# OpenLog.net
KiCad netlist of a schematic drawn in EAGLE
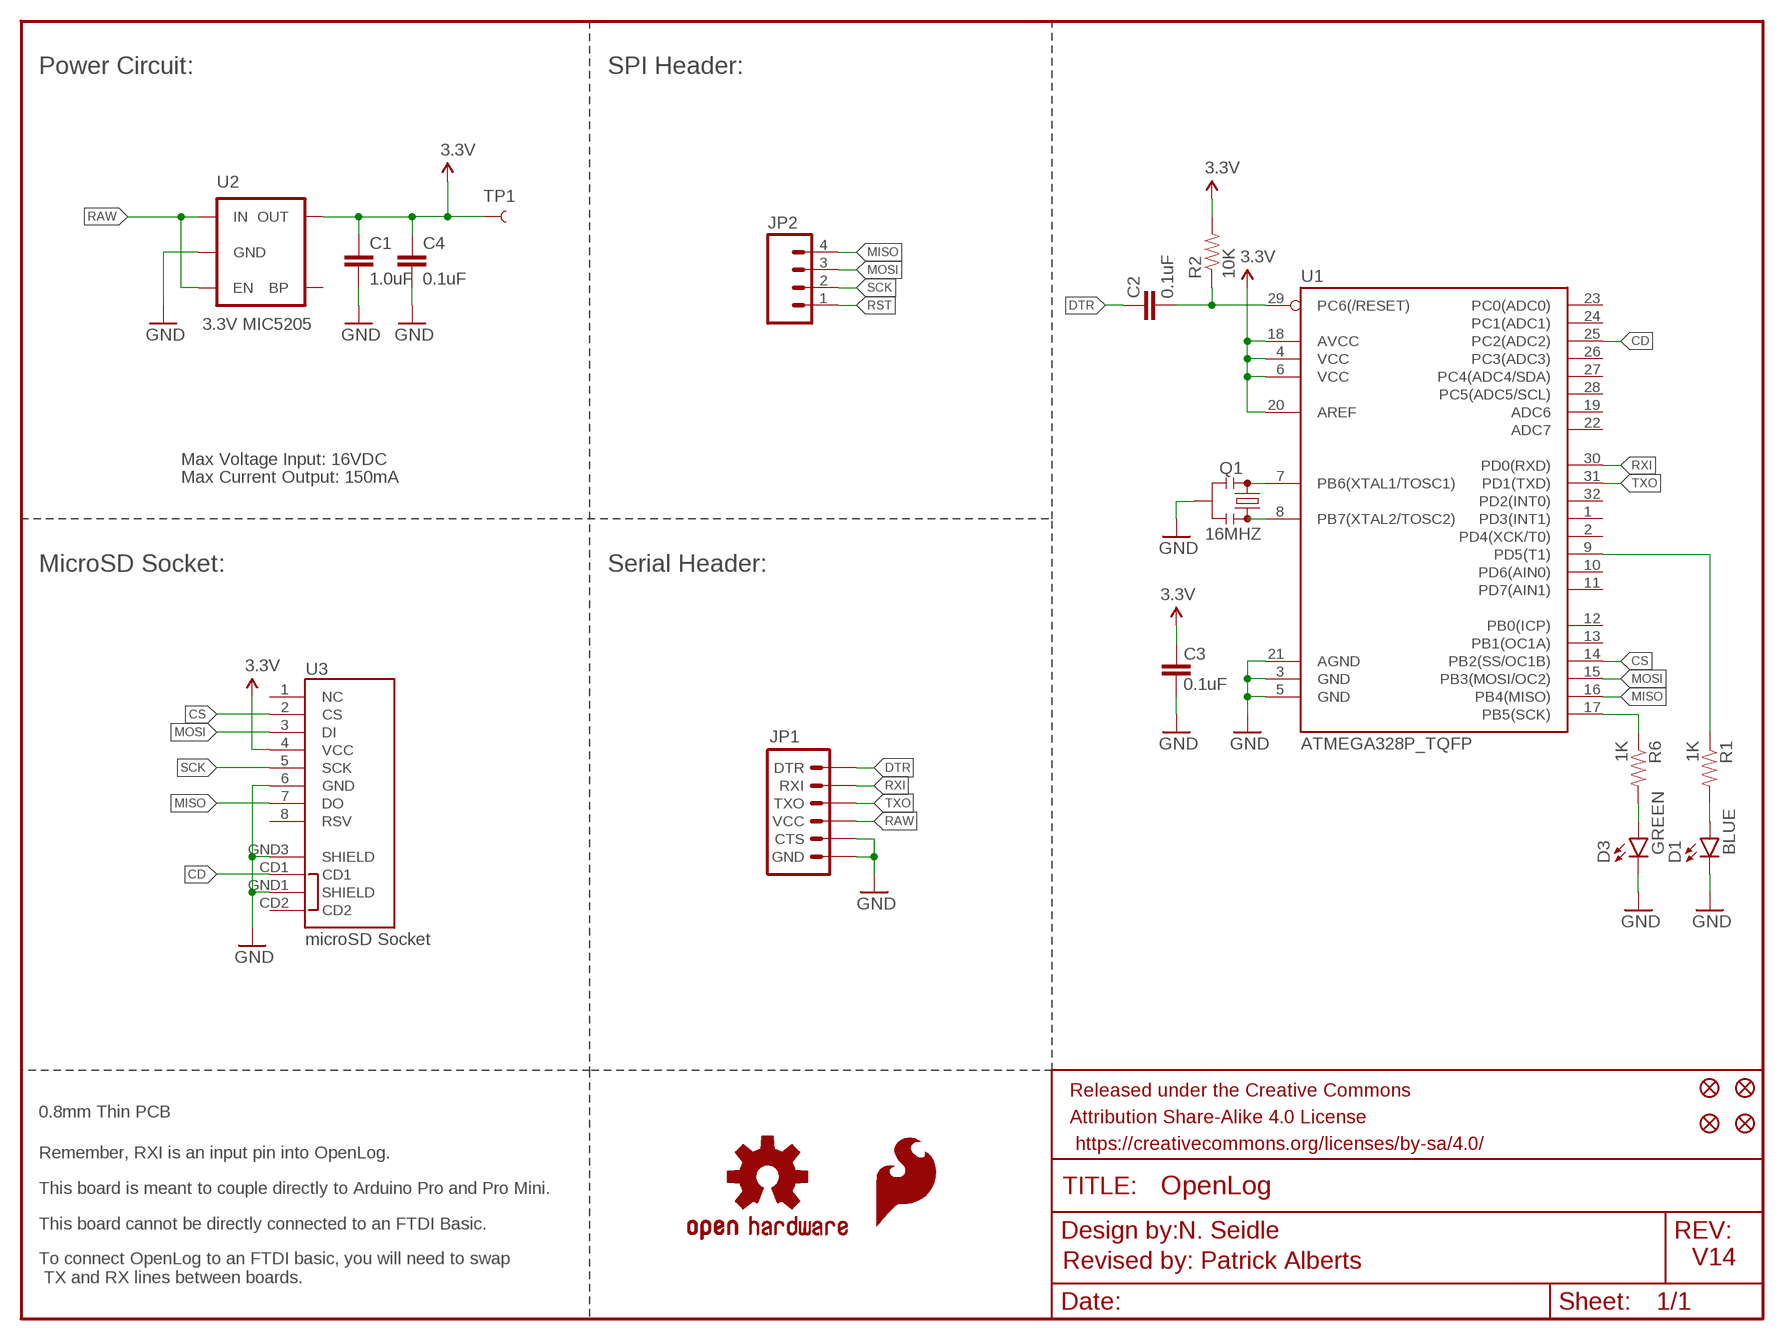
[diagram p0: schematic, sheet 1]

(export (version "E")
  (design (tool "Eeschema 10.0.6"))
  (components
    (comp (ref "C1")
      (value "1.0uF")
      (footprint "eagle-import:0603-CAP")
      (libsource (lib "eagle-import") (part "1.0UF-16V-10%(0603)"))
    )
    (comp (ref "C2")
      (value "0.1uF")
      (footprint "eagle-import:0603-CAP")
      (libsource (lib "eagle-import") (part "0.1UF-25V(+80/-20%)(0603)"))
    )
    (comp (ref "C3")
      (value "0.1uF")
      (footprint "eagle-import:0603-CAP")
      (libsource (lib "eagle-import") (part "0.1UF-25V(+80/-20%)(0603)"))
    )
    (comp (ref "C4")
      (value "0.1uF")
      (footprint "eagle-import:0603-CAP")
      (libsource (lib "eagle-import") (part "0.1UF-25V(+80/-20%)(0603)"))
    )
    (comp (ref "D1")
      (value "BLUE")
      (footprint "eagle-import:LED-0603")
      (libsource (lib "eagle-import") (part "LED-BLUE0603"))
    )
    (comp (ref "D3")
      (value "GREEN")
      (footprint "eagle-import:LED-0603")
      (libsource (lib "eagle-import") (part "LED-GREEN0603"))
    )
    (comp (ref "FID1")
      (value "FIDUCIALUFIDUCIAL")
      (footprint "eagle-import:MICRO-FIDUCIAL")
      (libsource (lib "eagle-import") (part "FIDUCIALUFIDUCIAL"))
    )
    (comp (ref "FID2")
      (value "FIDUCIALUFIDUCIAL")
      (footprint "eagle-import:MICRO-FIDUCIAL")
      (libsource (lib "eagle-import") (part "FIDUCIALUFIDUCIAL"))
    )
    (comp (ref "FID3")
      (value "FIDUCIALUFIDUCIAL")
      (footprint "eagle-import:MICRO-FIDUCIAL")
      (libsource (lib "eagle-import") (part "FIDUCIALUFIDUCIAL"))
    )
    (comp (ref "FID4")
      (value "FIDUCIALUFIDUCIAL")
      (footprint "eagle-import:MICRO-FIDUCIAL")
      (libsource (lib "eagle-import") (part "FIDUCIALUFIDUCIAL"))
    )
    (comp (ref "FRAME1")
      (value "FRAME-LETTER")
      (footprint "eagle-import:CREATIVE_COMMONS")
      (fields (field (name "DESIGNER") "NAME"))
      (libsource (lib "eagle-import") (part "FRAME-LETTER"))
    )
    (comp (ref "JP1")
      (value "Serial Connection")
      (footprint "eagle-import:1X06")
      (libsource (lib "eagle-import") (part "ARDUINO_SERIAL_PROGRAMPTH"))
    )
    (comp (ref "JP2")
      (value "M04PTH")
      (footprint "eagle-import:1X04")
      (libsource (lib "eagle-import") (part "M04PTH"))
    )
    (comp (ref "LOGO1")
      (value "SFE_LOGO_FLAME.1_INCH")
      (footprint "eagle-import:SFE_LOGO_FLAME_.1")
      (libsource (lib "eagle-import") (part "SFE_LOGO_FLAME.1_INCH"))
    )
    (comp (ref "LOGO2")
      (value "OSHW-LOGOS")
      (footprint "eagle-import:OSHW-LOGO-S")
      (libsource (lib "eagle-import") (part "OSHW-LOGOS"))
    )
    (comp (ref "Q1")
      (value "16MHZ")
      (footprint "eagle-import:RESONATOR-SMD")
      (libsource (lib "eagle-import") (part "RESONATOR16MHZ"))
    )
    (comp (ref "R1")
      (value "1K")
      (footprint "eagle-import:0603-RES")
      (libsource (lib "eagle-import") (part "1KOHM-1/10W-1%(0603)"))
    )
    (comp (ref "R2")
      (value "10K")
      (footprint "eagle-import:0603-RES")
      (libsource (lib "eagle-import") (part "10KOHM-1/10W-1%(0603)0603"))
    )
    (comp (ref "R6")
      (value "1K")
      (footprint "eagle-import:0603-RES")
      (libsource (lib "eagle-import") (part "1KOHM-1/10W-1%(0603)"))
    )
    (comp (ref "TP1")
      (value "TEST-POINT3")
      (footprint "eagle-import:PAD.03X.03")
      (libsource (lib "eagle-import") (part "TEST-POINT3"))
    )
    (comp (ref "U1")
      (value "ATMEGA328P_TQFP")
      (footprint "eagle-import:TQFP32-08")
      (libsource (lib "eagle-import") (part "ATMEGA328P_TQFP"))
    )
    (comp (ref "U2")
      (value "3.3V MIC5205")
      (footprint "eagle-import:SOT23-5")
      (libsource (lib "eagle-import") (part "MIC52053.3V"))
    )
    (comp (ref "U3")
      (value "microSD Socket")
      (footprint "eagle-import:MICROSD_1_1")
      (libsource (lib "eagle-import") (part "USD-SOCKET"))
    )
  )
  (nets
    (net (code "1") (name "3.3V") (class "Default")
      (node (ref "C1") (pin "1") (pinfunction "1_1") (pintype "passive"))
      (node (ref "C3") (pin "2") (pinfunction "2_2") (pintype "passive"))
      (node (ref "C4") (pin "1") (pinfunction "1_1") (pintype "passive"))
      (node (ref "R2") (pin "2") (pinfunction "2_2") (pintype "passive"))
      (node (ref "TP1") (pin "P$1") (pinfunction "1_P$1") (pintype "bidirectional"))
      (node (ref "U1") (pin "18") (pinfunction "AVCC_18") (pintype "bidirectional"))
      (node (ref "U1") (pin "20") (pinfunction "AREF_20") (pintype "bidirectional"))
      (node (ref "U1") (pin "4") (pinfunction "VCC_4") (pintype "bidirectional"))
      (node (ref "U1") (pin "6") (pinfunction "VCC_6") (pintype "bidirectional"))
      (node (ref "U2") (pin "5") (pinfunction "OUT_5") (pintype "passive"))
      (node (ref "U3") (pin "4") (pinfunction "VCC_4") (pintype "bidirectional"))
    )
    (net (code "2") (name "CD") (class "Default")
      (node (ref "U1") (pin "25") (pinfunction "PC2(ADC2)_25") (pintype "bidirectional"))
      (node (ref "U3") (pin "CD1") (pinfunction "CD1_CD1") (pintype "bidirectional"))
    )
    (net (code "3") (name "CS") (class "Default")
      (node (ref "U1") (pin "14") (pinfunction "PB2(SS/OC1B)_14") (pintype "bidirectional"))
      (node (ref "U3") (pin "2") (pinfunction "CS_2") (pintype "bidirectional"))
    )
    (net (code "4") (name "DTR") (class "Default")
      (node (ref "C2") (pin "2") (pinfunction "2_2") (pintype "passive"))
      (node (ref "JP1") (pin "1") (pinfunction "DTR_1") (pintype "passive"))
    )
    (net (code "5") (name "GND") (class "Default")
      (node (ref "C1") (pin "2") (pinfunction "2_2") (pintype "passive"))
      (node (ref "C3") (pin "1") (pinfunction "1_1") (pintype "passive"))
      (node (ref "C4") (pin "2") (pinfunction "2_2") (pintype "passive"))
      (node (ref "D1") (pin "C") (pinfunction "C_C") (pintype "passive"))
      (node (ref "D3") (pin "C") (pinfunction "C_C") (pintype "passive"))
      (node (ref "JP1") (pin "5") (pinfunction "CTS_5") (pintype "passive"))
      (node (ref "JP1") (pin "6") (pinfunction "GND_6") (pintype "passive"))
      (node (ref "Q1") (pin "2") (pinfunction "2_2") (pintype "passive"))
      (node (ref "U1") (pin "21") (pinfunction "AGND_21") (pintype "bidirectional"))
      (node (ref "U1") (pin "3") (pinfunction "GND_3") (pintype "bidirectional"))
      (node (ref "U1") (pin "5") (pinfunction "GND_5") (pintype "bidirectional"))
      (node (ref "U2") (pin "2") (pinfunction "GND_2") (pintype "input"))
      (node (ref "U3") (pin "6") (pinfunction "GND_6") (pintype "bidirectional"))
      (node (ref "U3") (pin "GND1") (pinfunction "SHIELD_GND1") (pintype "bidirectional"))
      (node (ref "U3") (pin "GND3") (pinfunction "SHIELD_GND3") (pintype "bidirectional"))
    )
    (net (code "6") (name "MISO") (class "Default")
      (node (ref "JP2") (pin "4") (pinfunction "4_4") (pintype "passive"))
      (node (ref "U1") (pin "16") (pinfunction "PB4(MISO)_16") (pintype "bidirectional"))
      (node (ref "U3") (pin "7") (pinfunction "DO_7") (pintype "bidirectional"))
    )
    (net (code "7") (name "MOSI") (class "Default")
      (node (ref "JP2") (pin "3") (pinfunction "3_3") (pintype "passive"))
      (node (ref "U1") (pin "15") (pinfunction "PB3(MOSI/OC2)_15") (pintype "bidirectional"))
      (node (ref "U3") (pin "3") (pinfunction "DI_3") (pintype "bidirectional"))
    )
    (net (code "8") (name "Net-(D1-PadA)") (class "Default")
      (node (ref "D1") (pin "A") (pinfunction "A_A") (pintype "passive"))
      (node (ref "R1") (pin "2") (pinfunction "2_2") (pintype "passive"))
    )
    (net (code "9") (name "Net-(D3-PadA)") (class "Default")
      (node (ref "D3") (pin "A") (pinfunction "A_A") (pintype "passive"))
      (node (ref "R6") (pin "2") (pinfunction "2_2") (pintype "passive"))
    )
    (net (code "10") (name "Net-(U1-PB6(XTAL1{slash}TOSC1))") (class "Default")
      (node (ref "Q1") (pin "3") (pinfunction "3_3") (pintype "passive"))
      (node (ref "U1") (pin "7") (pinfunction "PB6(XTAL1/TOSC1)_7") (pintype "bidirectional"))
    )
    (net (code "11") (name "Net-(U1-PB7(XTAL2{slash}TOSC2))") (class "Default")
      (node (ref "Q1") (pin "1") (pinfunction "1_1") (pintype "passive"))
      (node (ref "U1") (pin "8") (pinfunction "PB7(XTAL2/TOSC2)_8") (pintype "bidirectional"))
    )
    (net (code "12") (name "Net-(U1-PD5(T1))") (class "Default")
      (node (ref "R1") (pin "1") (pinfunction "1_1") (pintype "passive"))
      (node (ref "U1") (pin "9") (pinfunction "PD5(T1)_9") (pintype "bidirectional"))
    )
    (net (code "13") (name "RAW") (class "Default")
      (node (ref "JP1") (pin "4") (pinfunction "VCC_4") (pintype "passive"))
      (node (ref "U2") (pin "1") (pinfunction "IN_1") (pintype "input"))
      (node (ref "U2") (pin "3") (pinfunction "EN_3") (pintype "input"))
    )
    (net (code "14") (name "RST") (class "Default")
      (node (ref "C2") (pin "1") (pinfunction "1_1") (pintype "passive"))
      (node (ref "JP2") (pin "1") (pinfunction "1_1") (pintype "passive"))
      (node (ref "R2") (pin "1") (pinfunction "1_1") (pintype "passive"))
      (node (ref "U1") (pin "29") (pinfunction "PC6(/RESET)_29") (pintype "bidirectional"))
    )
    (net (code "15") (name "RXI") (class "Default")
      (node (ref "JP1") (pin "2") (pinfunction "RXI_2") (pintype "passive"))
      (node (ref "U1") (pin "30") (pinfunction "PD0(RXD)_30") (pintype "bidirectional"))
    )
    (net (code "16") (name "SCK") (class "Default")
      (node (ref "JP2") (pin "2") (pinfunction "2_2") (pintype "passive"))
      (node (ref "R6") (pin "1") (pinfunction "1_1") (pintype "passive"))
      (node (ref "U1") (pin "17") (pinfunction "PB5(SCK)_17") (pintype "bidirectional"))
      (node (ref "U3") (pin "5") (pinfunction "SCK_5") (pintype "bidirectional"))
    )
    (net (code "17") (name "TXO") (class "Default")
      (node (ref "JP1") (pin "3") (pinfunction "TXO_3") (pintype "passive"))
      (node (ref "U1") (pin "31") (pinfunction "PD1(TXD)_31") (pintype "bidirectional"))
    )
    (net (code "18") (name "unconnected-(U1-ADC6-Pad19)") (class "Default")
      (node (ref "U1") (pin "19") (pinfunction "ADC6_19") (pintype "bidirectional"))
    )
    (net (code "19") (name "unconnected-(U1-ADC7-Pad22)") (class "Default")
      (node (ref "U1") (pin "22") (pinfunction "ADC7_22") (pintype "bidirectional"))
    )
    (net (code "20") (name "unconnected-(U1-PB0(ICP)-Pad12)") (class "Default")
      (node (ref "U1") (pin "12") (pinfunction "PB0(ICP)_12") (pintype "bidirectional"))
    )
    (net (code "21") (name "unconnected-(U1-PB1(OC1A)-Pad13)") (class "Default")
      (node (ref "U1") (pin "13") (pinfunction "PB1(OC1A)_13") (pintype "bidirectional"))
    )
    (net (code "22") (name "unconnected-(U1-PC0(ADC0)-Pad23)") (class "Default")
      (node (ref "U1") (pin "23") (pinfunction "PC0(ADC0)_23") (pintype "bidirectional"))
    )
    (net (code "23") (name "unconnected-(U1-PC1(ADC1)-Pad24)") (class "Default")
      (node (ref "U1") (pin "24") (pinfunction "PC1(ADC1)_24") (pintype "bidirectional"))
    )
    (net (code "24") (name "unconnected-(U1-PC3(ADC3)-Pad26)") (class "Default")
      (node (ref "U1") (pin "26") (pinfunction "PC3(ADC3)_26") (pintype "bidirectional"))
    )
    (net (code "25") (name "unconnected-(U1-PC4(ADC4{slash}SDA)-Pad27)") (class "Default")
      (node (ref "U1") (pin "27") (pinfunction "PC4(ADC4/SDA)_27") (pintype "bidirectional"))
    )
    (net (code "26") (name "unconnected-(U1-PC5(ADC5{slash}SCL)-Pad28)") (class "Default")
      (node (ref "U1") (pin "28") (pinfunction "PC5(ADC5/SCL)_28") (pintype "bidirectional"))
    )
    (net (code "27") (name "unconnected-(U1-PD2(INT0)-Pad32)") (class "Default")
      (node (ref "U1") (pin "32") (pinfunction "PD2(INT0)_32") (pintype "bidirectional"))
    )
    (net (code "28") (name "unconnected-(U1-PD3(INT1)-Pad1)") (class "Default")
      (node (ref "U1") (pin "1") (pinfunction "PD3(INT1)_1") (pintype "bidirectional"))
    )
    (net (code "29") (name "unconnected-(U1-PD4(XCK{slash}T0)-Pad2)") (class "Default")
      (node (ref "U1") (pin "2") (pinfunction "PD4(XCK/T0)_2") (pintype "bidirectional"))
    )
    (net (code "30") (name "unconnected-(U1-PD6(AIN0)-Pad10)") (class "Default")
      (node (ref "U1") (pin "10") (pinfunction "PD6(AIN0)_10") (pintype "bidirectional"))
    )
    (net (code "31") (name "unconnected-(U1-PD7(AIN1)-Pad11)") (class "Default")
      (node (ref "U1") (pin "11") (pinfunction "PD7(AIN1)_11") (pintype "bidirectional"))
    )
    (net (code "32") (name "unconnected-(U2-BP-Pad4)") (class "Default")
      (node (ref "U2") (pin "4") (pinfunction "BP_4") (pintype "input"))
    )
    (net (code "33") (name "unconnected-(U3-NC-Pad1)") (class "Default")
      (node (ref "U3") (pin "1") (pinfunction "NC_1") (pintype "bidirectional"))
    )
    (net (code "34") (name "unconnected-(U3-PadCD2)") (class "Default")
      (node (ref "U3") (pin "CD2") (pinfunction "CD2_CD2") (pintype "bidirectional"))
    )
    (net (code "35") (name "unconnected-(U3-RSV-Pad8)") (class "Default")
      (node (ref "U3") (pin "8") (pinfunction "RSV_8") (pintype "bidirectional"))
    )
  )
)
